# Laser_Teensy4.net
KiCad netlist of a schematic drawn in EAGLE
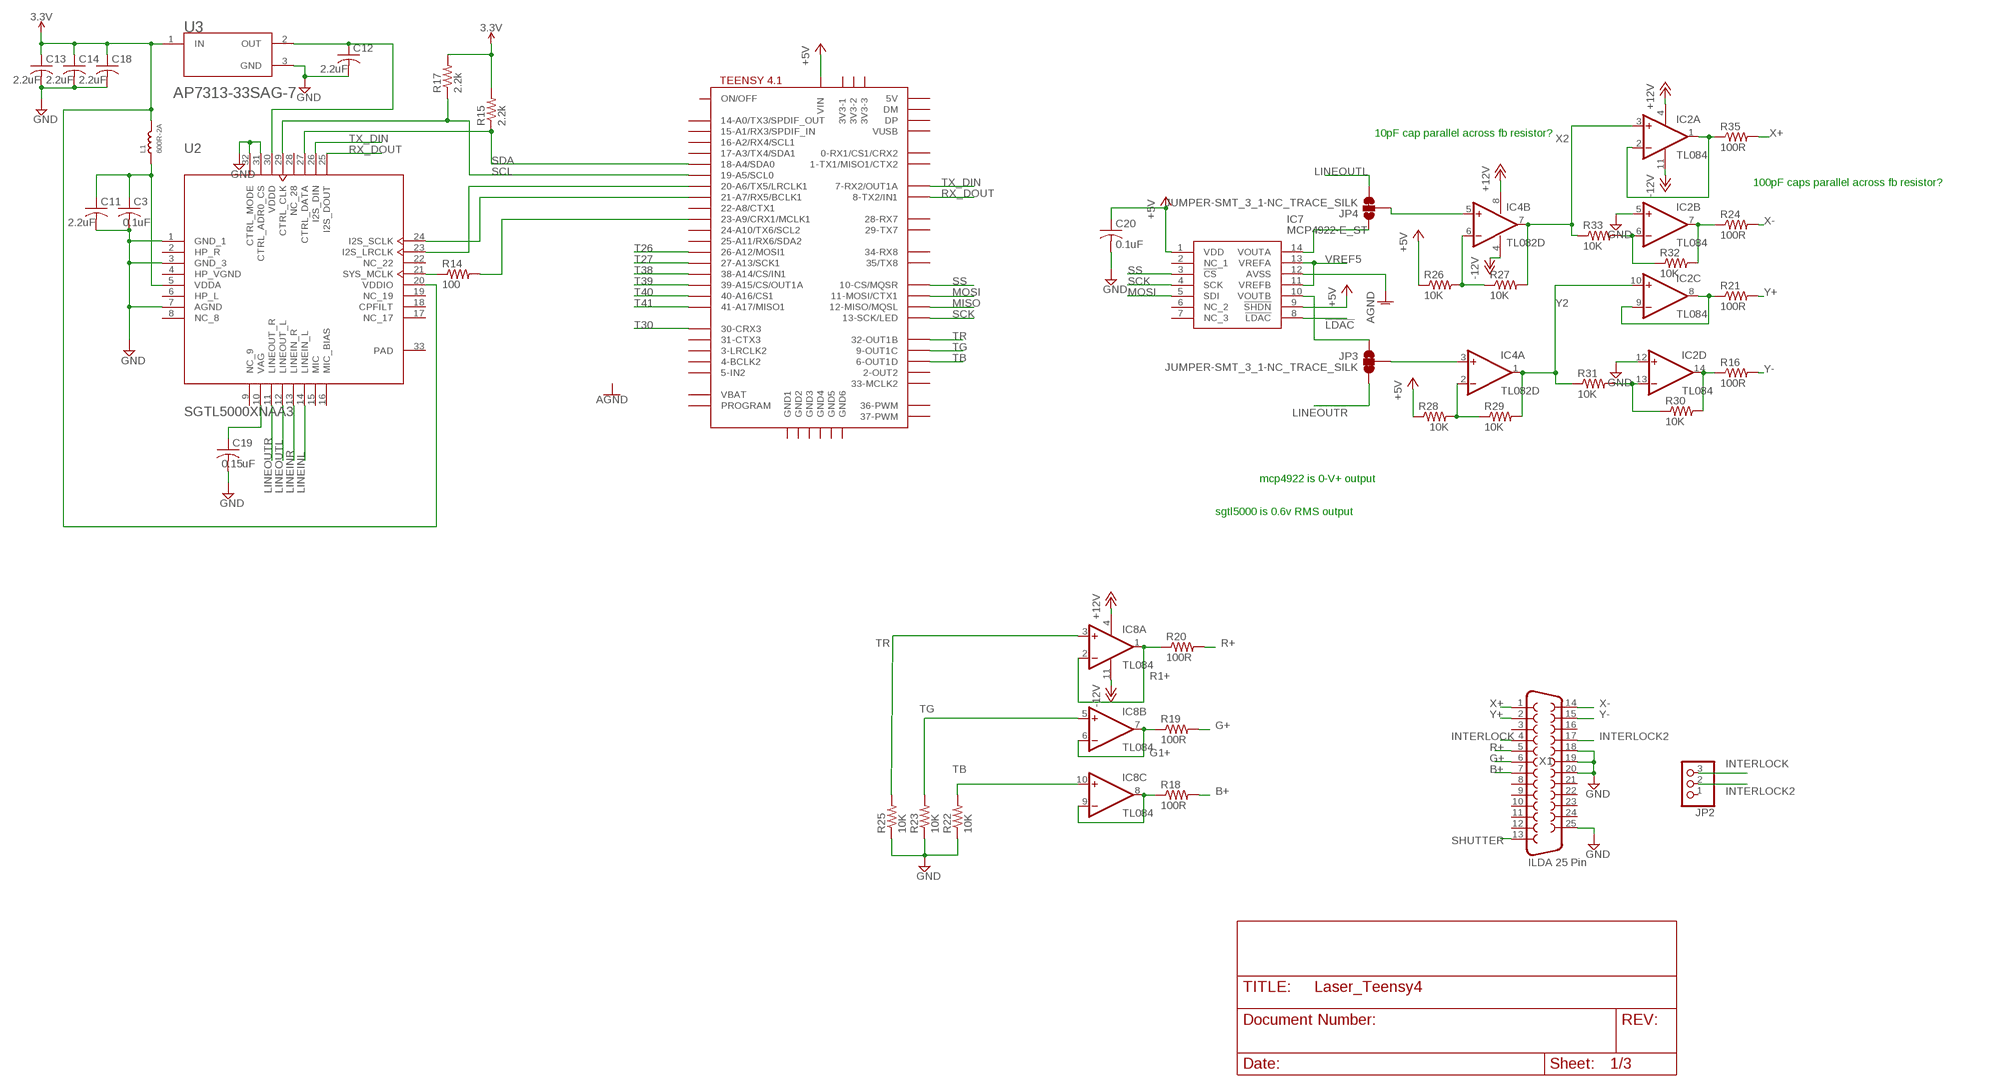
[diagram p0: schematic, sheet 1]
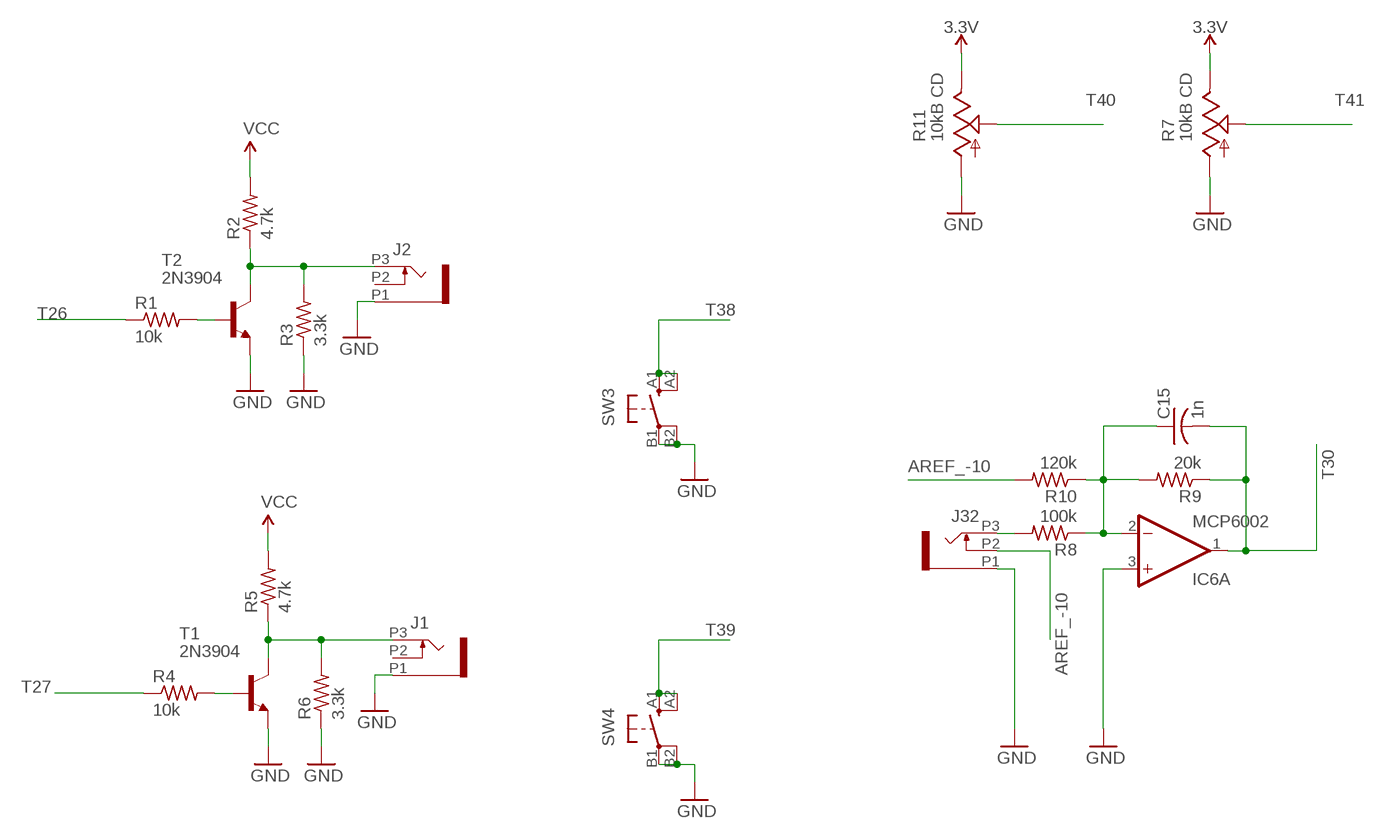
[diagram p1: schematic, sheet 2]
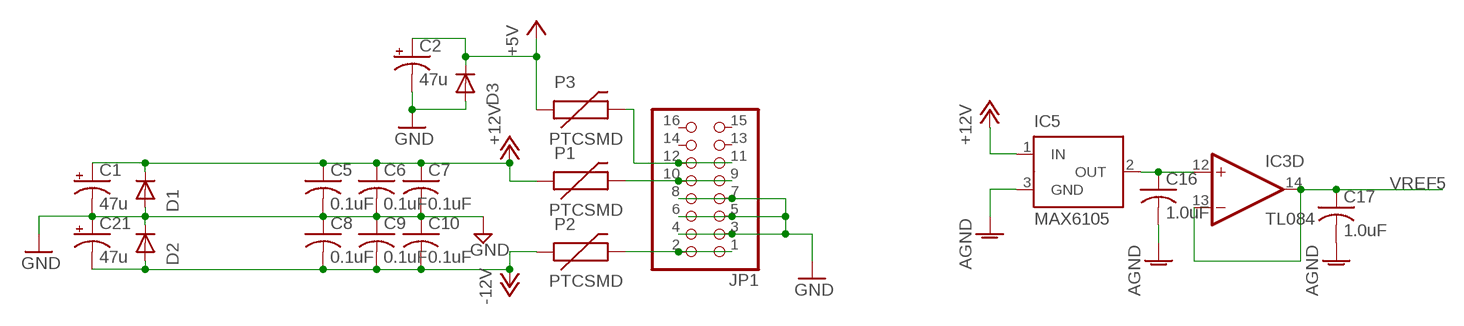
[diagram p2: schematic, sheet 3]

(export (version "E")
  (design (tool "Eeschema 10.0.6"))
  (components
    (comp (ref "C3")
      (value "0.1uF")
      (footprint "eagle-import:RCL_C0603")
      (libsource (lib "eagle-import") (part "RCL_C-USC0603"))
    )
    (comp (ref "C11")
      (value "2.2uF")
      (footprint "eagle-import:RCL_C0603")
      (libsource (lib "eagle-import") (part "RCL_C-USC0603"))
    )
    (comp (ref "C12")
      (value "2.2uF")
      (footprint "eagle-import:RCL_C0603")
      (libsource (lib "eagle-import") (part "RCL_C-USC0603"))
    )
    (comp (ref "C13")
      (value "2.2uF")
      (footprint "eagle-import:RCL_C0603")
      (libsource (lib "eagle-import") (part "RCL_C-USC0603"))
    )
    (comp (ref "C14")
      (value "2.2uF")
      (footprint "eagle-import:RCL_C0603")
      (libsource (lib "eagle-import") (part "RCL_C-USC0603"))
    )
    (comp (ref "C18")
      (value "2.2uF")
      (footprint "eagle-import:RCL_C0603")
      (libsource (lib "eagle-import") (part "RCL_C-USC0603"))
    )
    (comp (ref "C19")
      (value "0.15uF")
      (footprint "eagle-import:RCL_C0603")
      (libsource (lib "eagle-import") (part "RCL_C-USC0603"))
    )
    (comp (ref "C20")
      (value "0.1uF")
      (footprint "eagle-import:C0603")
      (libsource (lib "eagle-import") (part "C-USC0603"))
    )
    (comp (ref "IC2")
      (value "TL084")
      (footprint "eagle-import:SOIC-14")
      (libsource (lib "eagle-import") (part "TL084"))
    )
    (comp (ref "IC4")
      (value "TL082D")
      (footprint "eagle-import:SO08")
      (libsource (lib "eagle-import") (part "TL082D"))
    )
    (comp (ref "IC7")
      (value "MCP4922-E_ST")
      (footprint "eagle-import:SOP65P638X110-14N")
      (fields
        (field (name "ARROW_PART_NUMBER") "MCP4922-E/ST")
        (field (name "MOUSER_PART_NUMBER") "579-MCP4922-E/ST")
      )
      (libsource (lib "eagle-import") (part "MCP4922-E_ST"))
    )
    (comp (ref "IC8")
      (value "TL084")
      (footprint "eagle-import:SOIC-14")
      (libsource (lib "eagle-import") (part "TL084"))
    )
    (comp (ref "JP2")
      (value "PINHD-1X3")
      (footprint "eagle-import:1X03")
      (libsource (lib "eagle-import") (part "PINHD-1X3"))
    )
    (comp (ref "JP3")
      (value "JUMPER-SMT_3_1-NC_TRACE_SILK")
      (footprint "eagle-import:SMT-JUMPER_3_1-NC_TRACE_SILK")
      (libsource (lib "eagle-import") (part "JUMPER-SMT_3_1-NC_TRACE_SILK"))
    )
    (comp (ref "JP4")
      (value "JUMPER-SMT_3_1-NC_TRACE_SILK")
      (footprint "eagle-import:SMT-JUMPER_3_1-NC_TRACE_SILK")
      (libsource (lib "eagle-import") (part "JUMPER-SMT_3_1-NC_TRACE_SILK"))
    )
    (comp (ref "L1")
      (value "600R-2A")
      (footprint "eagle-import:L0805")
      (fields (field (name "MPN") "WLB2012-471T20"))
      (libsource (lib "eagle-import") (part "SMD-FERRITE-BEAD-470R-2A(0805)'0805'"))
    )
    (comp (ref "R14")
      (value "100")
      (footprint "eagle-import:R0603")
      (libsource (lib "eagle-import") (part "resistor_R-US_R0603"))
    )
    (comp (ref "R15")
      (value "2.2k")
      (footprint "eagle-import:R0603")
      (libsource (lib "eagle-import") (part "resistor_R-US_R0603"))
    )
    (comp (ref "R16")
      (value "100R")
      (footprint "eagle-import:R0603")
      (libsource (lib "eagle-import") (part "resistor_R-US_R0603"))
    )
    (comp (ref "R17")
      (value "2.2k")
      (footprint "eagle-import:R0603")
      (libsource (lib "eagle-import") (part "resistor_R-US_R0603"))
    )
    (comp (ref "R18")
      (value "100R")
      (footprint "eagle-import:R0603")
      (libsource (lib "eagle-import") (part "resistor_R-US_R0603"))
    )
    (comp (ref "R19")
      (value "100R")
      (footprint "eagle-import:R0603")
      (libsource (lib "eagle-import") (part "resistor_R-US_R0603"))
    )
    (comp (ref "R20")
      (value "100R")
      (footprint "eagle-import:R0603")
      (libsource (lib "eagle-import") (part "resistor_R-US_R0603"))
    )
    (comp (ref "R21")
      (value "100R")
      (footprint "eagle-import:R0603")
      (libsource (lib "eagle-import") (part "resistor_R-US_R0603"))
    )
    (comp (ref "R22")
      (value "10K")
      (footprint "eagle-import:R0603")
      (libsource (lib "eagle-import") (part "resistor_R-US_R0603"))
    )
    (comp (ref "R23")
      (value "10K")
      (footprint "eagle-import:R0603")
      (libsource (lib "eagle-import") (part "resistor_R-US_R0603"))
    )
    (comp (ref "R24")
      (value "100R")
      (footprint "eagle-import:R0603")
      (libsource (lib "eagle-import") (part "resistor_R-US_R0603"))
    )
    (comp (ref "R25")
      (value "10K")
      (footprint "eagle-import:R0603")
      (libsource (lib "eagle-import") (part "resistor_R-US_R0603"))
    )
    (comp (ref "R26")
      (value "10K")
      (footprint "eagle-import:R0603")
      (libsource (lib "eagle-import") (part "resistor_R-US_R0603"))
    )
    (comp (ref "R27")
      (value "10K")
      (footprint "eagle-import:R0603")
      (libsource (lib "eagle-import") (part "resistor_R-US_R0603"))
    )
    (comp (ref "R28")
      (value "10K")
      (footprint "eagle-import:R0603")
      (libsource (lib "eagle-import") (part "resistor_R-US_R0603"))
    )
    (comp (ref "R29")
      (value "10K")
      (footprint "eagle-import:R0603")
      (libsource (lib "eagle-import") (part "resistor_R-US_R0603"))
    )
    (comp (ref "R30")
      (value "10K")
      (footprint "eagle-import:R0603")
      (libsource (lib "eagle-import") (part "resistor_R-US_R0603"))
    )
    (comp (ref "R31")
      (value "10K")
      (footprint "eagle-import:R0603")
      (libsource (lib "eagle-import") (part "resistor_R-US_R0603"))
    )
    (comp (ref "R32")
      (value "10K")
      (footprint "eagle-import:R0603")
      (libsource (lib "eagle-import") (part "resistor_R-US_R0603"))
    )
    (comp (ref "R33")
      (value "10K")
      (footprint "eagle-import:R0603")
      (libsource (lib "eagle-import") (part "resistor_R-US_R0603"))
    )
    (comp (ref "R35")
      (value "100R")
      (footprint "eagle-import:R0603")
      (libsource (lib "eagle-import") (part "resistor_R-US_R0603"))
    )
    (comp (ref "U$2")
      (value "TEENSY41-E")
      (footprint "eagle-import:TENNSY41-E")
      (libsource (lib "eagle-import") (part "TEENSY41-E"))
    )
    (comp (ref "U2")
      (value "SGTL5000XNAA3")
      (footprint "eagle-import:QFN-32")
      (fields
        (field (name "DIGIKEY_PART_NUMBER") "SGTL5000XNAA3-ND")
        (field (name "MANUFACTURER") "NXP USA Inc.")
        (field (name "CREATED_BY") "PCBLayout.com")
      )
      (libsource (lib "eagle-import") (part "SGTL5000XNAA3"))
    )
    (comp (ref "U3")
      (value "DIODES_INC_AP7313-33SAG-7DIODES_INC_AP7313-33SAG-7_0_3")
      (footprint "eagle-import:DIODES_INC_AP7313-33SAG-7_3")
      (fields
        (field (name "DIGIKEY_PART_NUMBER") "AP7313-33SAG-7DICT-ND")
        (field (name "MF") "Diodes Inc.")
        (field (name "MOUSER_PART_NUMBER") "621-AP7313-33SAG-7")
      )
      (libsource (lib "eagle-import") (part "DIODES_INC_AP7313-33SAG-7DIODES_INC_AP7313-33SAG-7_0_3"))
    )
    (comp (ref "X1")
      (value "ILDA 25 Pin")
      (footprint "eagle-import:F25D")
      (libsource (lib "eagle-import") (part "F25D"))
    )
    (comp (ref "C15")
      (value "1n")
      (footprint "eagle-import:C050-025X075")
      (libsource (lib "eagle-import") (part "rcl_334_C-US050-025X075"))
    )
    (comp (ref "IC6")
      (value "MCP6002")
      (footprint "eagle-import:SO08")
      (libsource (lib "eagle-import") (part "TL072D"))
    )
    (comp (ref "J1")
      (value "PJ301_THONKICONN6")
      (footprint "eagle-import:WQP_PJ_301M6")
      (libsource (lib "eagle-import") (part "PJ301_THONKICONN6"))
    )
    (comp (ref "J2")
      (value "PJ301_THONKICONN6")
      (footprint "eagle-import:WQP_PJ_301M6")
      (libsource (lib "eagle-import") (part "PJ301_THONKICONN6"))
    )
    (comp (ref "J32")
      (value "PJ301_THONKICONN6")
      (footprint "eagle-import:WQP_PJ_301M6")
      (libsource (lib "eagle-import") (part "PJ301_THONKICONN6"))
    )
    (comp (ref "R1")
      (value "10k")
      (footprint "eagle-import:0204_7")
      (libsource (lib "eagle-import") (part "R-US_0204/7"))
    )
    (comp (ref "R2")
      (value "4.7k")
      (footprint "eagle-import:0204_7")
      (libsource (lib "eagle-import") (part "R-US_0204/7"))
    )
    (comp (ref "R3")
      (value "3.3k")
      (footprint "eagle-import:0204_7")
      (libsource (lib "eagle-import") (part "R-US_0204/7"))
    )
    (comp (ref "R4")
      (value "10k")
      (footprint "eagle-import:0204_7")
      (libsource (lib "eagle-import") (part "R-US_0204/7"))
    )
    (comp (ref "R5")
      (value "4.7k")
      (footprint "eagle-import:0204_7")
      (libsource (lib "eagle-import") (part "R-US_0204/7"))
    )
    (comp (ref "R6")
      (value "3.3k")
      (footprint "eagle-import:0204_7")
      (libsource (lib "eagle-import") (part "R-US_0204/7"))
    )
    (comp (ref "R7")
      (value "10kB CD")
      (footprint "eagle-import:ALPS_POT_VERTICAL_PS")
      (libsource (lib "eagle-import") (part "POT_USVERTICAL_PS"))
    )
    (comp (ref "R8")
      (value "100k")
      (footprint "eagle-import:0204_7")
      (libsource (lib "eagle-import") (part "R-US_0204/7"))
    )
    (comp (ref "R9")
      (value "20k")
      (footprint "eagle-import:0204_7")
      (libsource (lib "eagle-import") (part "R-US_0204/7"))
    )
    (comp (ref "R10")
      (value "120k")
      (footprint "eagle-import:0204_7")
      (libsource (lib "eagle-import") (part "R-US_0204/7"))
    )
    (comp (ref "R11")
      (value "10kB CD")
      (footprint "eagle-import:ALPS_POT_VERTICAL_PS")
      (libsource (lib "eagle-import") (part "POT_USVERTICAL_PS"))
    )
    (comp (ref "SW3")
      (value "D6R")
      (footprint "eagle-import:D6R")
      (libsource (lib "eagle-import") (part "D6R"))
    )
    (comp (ref "SW4")
      (value "D6R")
      (footprint "eagle-import:D6R")
      (libsource (lib "eagle-import") (part "D6R"))
    )
    (comp (ref "T1")
      (value "2N3904")
      (footprint "eagle-import:TO92")
      (libsource (lib "eagle-import") (part "2N3904"))
    )
    (comp (ref "T2")
      (value "2N3904")
      (footprint "eagle-import:TO92")
      (libsource (lib "eagle-import") (part "2N3904"))
    )
    (comp (ref "C1")
      (value "47u")
      (footprint "eagle-import:PANASONIC_D")
      (libsource (lib "eagle-import") (part "CPOL-USD"))
    )
    (comp (ref "C2")
      (value "47u")
      (footprint "eagle-import:PANASONIC_D")
      (libsource (lib "eagle-import") (part "CPOL-USD"))
    )
    (comp (ref "C5")
      (value "0.1uF")
      (footprint "eagle-import:C0603")
      (libsource (lib "eagle-import") (part "C-USC0603"))
    )
    (comp (ref "C6")
      (value "0.1uF")
      (footprint "eagle-import:C0603")
      (libsource (lib "eagle-import") (part "C-USC0603"))
    )
    (comp (ref "C7")
      (value "0.1uF")
      (footprint "eagle-import:C0603")
      (libsource (lib "eagle-import") (part "C-USC0603"))
    )
    (comp (ref "C8")
      (value "0.1uF")
      (footprint "eagle-import:C0603")
      (libsource (lib "eagle-import") (part "C-USC0603"))
    )
    (comp (ref "C9")
      (value "0.1uF")
      (footprint "eagle-import:C0603")
      (libsource (lib "eagle-import") (part "C-USC0603"))
    )
    (comp (ref "C10")
      (value "0.1uF")
      (footprint "eagle-import:C0603")
      (libsource (lib "eagle-import") (part "C-USC0603"))
    )
    (comp (ref "C16")
      (value "1.0uF")
      (footprint "eagle-import:C025-024X044")
      (libsource (lib "eagle-import") (part "C-US025-024X044"))
    )
    (comp (ref "C17")
      (value "1.0uF")
      (footprint "eagle-import:C025-024X044")
      (libsource (lib "eagle-import") (part "C-US025-024X044"))
    )
    (comp (ref "C21")
      (value "47u")
      (footprint "eagle-import:PANASONIC_D")
      (libsource (lib "eagle-import") (part "CPOL-USD"))
    )
    (comp (ref "D1")
      (value "1N5819HW")
      (footprint "eagle-import:SOD123")
      (libsource (lib "eagle-import") (part "DIODE-SOD123"))
    )
    (comp (ref "D2")
      (value "1N5819HW")
      (footprint "eagle-import:SOD123")
      (libsource (lib "eagle-import") (part "DIODE-SOD123"))
    )
    (comp (ref "D3")
      (value "1N5819HW")
      (footprint "eagle-import:SOD123")
      (libsource (lib "eagle-import") (part "DIODE-SOD123"))
    )
    (comp (ref "IC3")
      (value "TL084")
      (footprint "eagle-import:SOIC-14")
      (libsource (lib "eagle-import") (part "TL084"))
    )
    (comp (ref "IC5")
      (value "MAX6105")
      (footprint "eagle-import:SOT23")
      (libsource (lib "eagle-import") (part "MAX6520"))
    )
    (comp (ref "JP1")
      (value "PINHD-2X8")
      (footprint "eagle-import:2X08")
      (libsource (lib "eagle-import") (part "PINHD-2X8"))
    )
    (comp (ref "P1")
      (value "PTCSMD")
      (footprint "eagle-import:PTC-1206")
      (libsource (lib "eagle-import") (part "PTCSMD"))
    )
    (comp (ref "P2")
      (value "PTCSMD")
      (footprint "eagle-import:PTC-1206")
      (libsource (lib "eagle-import") (part "PTCSMD"))
    )
    (comp (ref "P3")
      (value "PTCSMD")
      (footprint "eagle-import:PTC-1206")
      (libsource (lib "eagle-import") (part "PTCSMD"))
    )
  )
  (nets
    (net (code "1") (name "+5V") (class "Default")
      (node (ref "C2") (pin "+") (pinfunction "+_+") (pintype "passive"))
      (node (ref "C20") (pin "1") (pinfunction "1_1") (pintype "passive"))
      (node (ref "D3") (pin "C") (pinfunction "C_C") (pintype "passive"))
      (node (ref "IC7") (pin "1") (pinfunction "VDD_1") (pintype "bidirectional"))
      (node (ref "IC7") (pin "9") (pinfunction "~{SHDN}_9") (pintype "bidirectional"))
      (node (ref "P3") (pin "1") (pinfunction "1_1") (pintype "bidirectional"))
      (node (ref "R26") (pin "1") (pinfunction "1_1") (pintype "passive"))
      (node (ref "R28") (pin "1") (pinfunction "1_1") (pintype "passive"))
      (node (ref "U$2") (pin "VIN") (pinfunction "VIN_VIN") (pintype "bidirectional"))
    )
    (net (code "2") (name "+12V") (class "Default")
      (node (ref "C1") (pin "+") (pinfunction "+_+") (pintype "passive"))
      (node (ref "C5") (pin "1") (pinfunction "1_1") (pintype "passive"))
      (node (ref "C6") (pin "1") (pinfunction "1_1") (pintype "passive"))
      (node (ref "C7") (pin "1") (pinfunction "1_1") (pintype "passive"))
      (node (ref "D1") (pin "C") (pinfunction "C_C") (pintype "passive"))
      (node (ref "IC2") (pin "4") (pinfunction "V+_4") (pintype "power_in"))
      (node (ref "IC4") (pin "8") (pinfunction "V+_8") (pintype "power_in"))
      (node (ref "IC5") (pin "1") (pinfunction "IN_1") (pintype "input"))
      (node (ref "IC8") (pin "4") (pinfunction "V+_4") (pintype "power_in"))
      (node (ref "P1") (pin "1") (pinfunction "1_1") (pintype "bidirectional"))
    )
    (net (code "3") (name "-12V") (class "Default")
      (node (ref "C10") (pin "2") (pinfunction "2_2") (pintype "passive"))
      (node (ref "C21") (pin "-") (pinfunction "-_-") (pintype "passive"))
      (node (ref "C8") (pin "2") (pinfunction "2_2") (pintype "passive"))
      (node (ref "C9") (pin "2") (pinfunction "2_2") (pintype "passive"))
      (node (ref "D2") (pin "A") (pinfunction "A_A") (pintype "passive"))
      (node (ref "IC2") (pin "11") (pinfunction "V-_11") (pintype "power_in"))
      (node (ref "IC4") (pin "4") (pinfunction "V-_4") (pintype "power_in"))
      (node (ref "IC8") (pin "11") (pinfunction "V-_11") (pintype "power_in"))
      (node (ref "P2") (pin "1") (pinfunction "1_1") (pintype "bidirectional"))
    )
    (net (code "4") (name "3.3V") (class "Default")
      (node (ref "C13") (pin "1") (pinfunction "1_1") (pintype "passive"))
      (node (ref "C14") (pin "1") (pinfunction "1_1") (pintype "passive"))
      (node (ref "C18") (pin "1") (pinfunction "1_1") (pintype "passive"))
      (node (ref "L1") (pin "2") (pinfunction "2_2") (pintype "passive"))
      (node (ref "R11") (pin "P$1") (pinfunction "E_P$1") (pintype "passive"))
      (node (ref "R15") (pin "2") (pinfunction "2_2") (pintype "passive"))
      (node (ref "R17") (pin "2") (pinfunction "2_2") (pintype "passive"))
      (node (ref "R7") (pin "P$1") (pinfunction "E_P$1") (pintype "passive"))
      (node (ref "U2") (pin "20") (pinfunction "VDDIO_20") (pintype "power_in"))
      (node (ref "U3") (pin "1") (pinfunction "IN_1") (pintype "power_in"))
    )
    (net (code "5") (name "AGND") (class "Default")
      (node (ref "C16") (pin "2") (pinfunction "2_2") (pintype "passive"))
      (node (ref "C17") (pin "2") (pinfunction "2_2") (pintype "passive"))
      (node (ref "IC5") (pin "3") (pinfunction "GND_3") (pintype "power_in"))
      (node (ref "IC7") (pin "12") (pinfunction "AVSS_12") (pintype "bidirectional"))
    )
    (net (code "6") (name "AREF_-10") (class "Default")
      (node (ref "J32") (pin "P2") (pinfunction "2_P2") (pintype "passive"))
      (node (ref "R10") (pin "2") (pinfunction "2_2") (pintype "passive"))
    )
    (net (code "7") (name "B+") (class "Default")
      (node (ref "R18") (pin "2") (pinfunction "2_2") (pintype "passive"))
      (node (ref "X1") (pin "7") (pinfunction "7_7") (pintype "passive"))
    )
    (net (code "8") (name "G+") (class "Default")
      (node (ref "R19") (pin "2") (pinfunction "2_2") (pintype "passive"))
      (node (ref "X1") (pin "6") (pinfunction "6_6") (pintype "passive"))
    )
    (net (code "9") (name "G1+") (class "Default")
      (node (ref "IC8") (pin "6") (pinfunction "-IN_6") (pintype "input"))
      (node (ref "IC8") (pin "7") (pinfunction "OUT_7") (pintype "output"))
      (node (ref "R19") (pin "1") (pinfunction "1_1") (pintype "passive"))
    )
    (net (code "10") (name "GND") (class "Default")
      (node (ref "C1") (pin "-") (pinfunction "-_-") (pintype "passive"))
      (node (ref "C10") (pin "1") (pinfunction "1_1") (pintype "passive"))
      (node (ref "C11") (pin "2") (pinfunction "2_2") (pintype "passive"))
      (node (ref "C12") (pin "2") (pinfunction "2_2") (pintype "passive"))
      (node (ref "C13") (pin "2") (pinfunction "2_2") (pintype "passive"))
      (node (ref "C14") (pin "2") (pinfunction "2_2") (pintype "passive"))
      (node (ref "C18") (pin "2") (pinfunction "2_2") (pintype "passive"))
      (node (ref "C19") (pin "2") (pinfunction "2_2") (pintype "passive"))
      (node (ref "C2") (pin "-") (pinfunction "-_-") (pintype "passive"))
      (node (ref "C20") (pin "2") (pinfunction "2_2") (pintype "passive"))
      (node (ref "C21") (pin "+") (pinfunction "+_+") (pintype "passive"))
      (node (ref "C3") (pin "2") (pinfunction "2_2") (pintype "passive"))
      (node (ref "C5") (pin "2") (pinfunction "2_2") (pintype "passive"))
      (node (ref "C6") (pin "2") (pinfunction "2_2") (pintype "passive"))
      (node (ref "C7") (pin "2") (pinfunction "2_2") (pintype "passive"))
      (node (ref "C8") (pin "1") (pinfunction "1_1") (pintype "passive"))
      (node (ref "C9") (pin "1") (pinfunction "1_1") (pintype "passive"))
      (node (ref "D1") (pin "A") (pinfunction "A_A") (pintype "passive"))
      (node (ref "D2") (pin "C") (pinfunction "C_C") (pintype "passive"))
      (node (ref "D3") (pin "A") (pinfunction "A_A") (pintype "passive"))
      (node (ref "IC2") (pin "12") (pinfunction "+IN_12") (pintype "input"))
      (node (ref "IC2") (pin "5") (pinfunction "+IN_5") (pintype "input"))
      (node (ref "IC6") (pin "3") (pinfunction "+IN_3") (pintype "input"))
      (node (ref "J1") (pin "P1") (pinfunction "1_P1") (pintype "passive"))
      (node (ref "J2") (pin "P1") (pinfunction "1_P1") (pintype "passive"))
      (node (ref "J32") (pin "P1") (pinfunction "1_P1") (pintype "passive"))
      (node (ref "JP1") (pin "3") (pinfunction "3_3") (pintype "passive"))
      (node (ref "JP1") (pin "4") (pinfunction "4_4") (pintype "passive"))
      (node (ref "JP1") (pin "5") (pinfunction "5_5") (pintype "passive"))
      (node (ref "JP1") (pin "6") (pinfunction "6_6") (pintype "passive"))
      (node (ref "JP1") (pin "7") (pinfunction "7_7") (pintype "passive"))
      (node (ref "JP1") (pin "8") (pinfunction "8_8") (pintype "passive"))
      (node (ref "R11") (pin "P$3") (pinfunction "A_P$3") (pintype "passive"))
      (node (ref "R22") (pin "1") (pinfunction "1_1") (pintype "passive"))
      (node (ref "R23") (pin "1") (pinfunction "1_1") (pintype "passive"))
      (node (ref "R25") (pin "1") (pinfunction "1_1") (pintype "passive"))
      (node (ref "R3") (pin "1") (pinfunction "1_1") (pintype "passive"))
      (node (ref "R6") (pin "1") (pinfunction "1_1") (pintype "passive"))
      (node (ref "R7") (pin "P$3") (pinfunction "A_P$3") (pintype "passive"))
      (node (ref "SW3") (pin "B1") (pinfunction "P_B1") (pintype "passive"))
      (node (ref "SW3") (pin "B2") (pinfunction "P1_B2") (pintype "passive"))
      (node (ref "SW4") (pin "B1") (pinfunction "P_B1") (pintype "passive"))
      (node (ref "SW4") (pin "B2") (pinfunction "P1_B2") (pintype "passive"))
      (node (ref "T1") (pin "3") (pinfunction "E_3") (pintype "passive"))
      (node (ref "T2") (pin "3") (pinfunction "E_3") (pintype "passive"))
      (node (ref "U2") (pin "1") (pinfunction "GND_1_1") (pintype "power_in"))
      (node (ref "U2") (pin "3") (pinfunction "GND_3_3") (pintype "power_in"))
      (node (ref "U2") (pin "31") (pinfunction "CTRL_ADR0_CS_31") (pintype "input"))
      (node (ref "U2") (pin "32") (pinfunction "CTRL_MODE_32") (pintype "bidirectional"))
      (node (ref "U2") (pin "7") (pinfunction "AGND_7") (pintype "power_in"))
      (node (ref "U3") (pin "3") (pinfunction "GND_3") (pintype "power_in"))
      (node (ref "X1") (pin "18") (pinfunction "18_18") (pintype "passive"))
      (node (ref "X1") (pin "19") (pinfunction "19_19") (pintype "passive"))
      (node (ref "X1") (pin "20") (pinfunction "20_20") (pintype "passive"))
      (node (ref "X1") (pin "25") (pinfunction "25_25") (pintype "passive"))
    )
    (net (code "11") (name "HP_VGND") (class "Default")
      (node (ref "U2") (pin "4") (pinfunction "HP_VGND_4") (pintype "power_in"))
    )
    (net (code "12") (name "INTERLOCK") (class "Default")
      (node (ref "JP2") (pin "3") (pinfunction "3_3") (pintype "passive"))
      (node (ref "X1") (pin "4") (pinfunction "4_4") (pintype "passive"))
    )
    (net (code "13") (name "INTERLOCK2") (class "Default")
      (node (ref "JP2") (pin "2") (pinfunction "2_2") (pintype "passive"))
      (node (ref "X1") (pin "17") (pinfunction "17_17") (pintype "passive"))
    )
    (net (code "14") (name "LINEINL") (class "Default")
      (node (ref "U2") (pin "14") (pinfunction "LINEIN_L_14") (pintype "input"))
    )
    (net (code "15") (name "LINEINR") (class "Default")
      (node (ref "U2") (pin "13") (pinfunction "LINEIN_R_13") (pintype "input"))
    )
    (net (code "16") (name "LINEOUTL") (class "Default")
      (node (ref "JP4") (pin "3") (pinfunction "3_3") (pintype "passive"))
      (node (ref "U2") (pin "12") (pinfunction "LINEOUT_L_12") (pintype "output"))
    )
    (net (code "17") (name "LINEOUTR") (class "Default")
      (node (ref "JP3") (pin "3") (pinfunction "3_3") (pintype "passive"))
      (node (ref "U2") (pin "11") (pinfunction "LINEOUT_R_11") (pintype "output"))
    )
    (net (code "18") (name "MISO") (class "Default")
      (node (ref "U$2") (pin "12-MISO/MQSL") (pinfunction "12-MISO/MQSL_12-MISO/MQSL") (pintype "bidirectional"))
    )
    (net (code "19") (name "MOSI") (class "Default")
      (node (ref "IC7") (pin "5") (pinfunction "SDI_5") (pintype "bidirectional"))
      (node (ref "U$2") (pin "11-MOSI/CTX1") (pinfunction "11-MOSI/CTX1_11-MOSI/CTX1") (pintype "bidirectional"))
    )
    (net (code "20") (name "Net-(IC2A--IN)") (class "Default")
      (node (ref "IC2") (pin "1") (pinfunction "OUT_1") (pintype "output"))
      (node (ref "IC2") (pin "2") (pinfunction "-IN_2") (pintype "input"))
      (node (ref "R35") (pin "1") (pinfunction "1_1") (pintype "passive"))
    )
    (net (code "21") (name "Net-(IC2B--IN)") (class "Default")
      (node (ref "IC2") (pin "6") (pinfunction "-IN_6") (pintype "input"))
      (node (ref "R32") (pin "1") (pinfunction "1_1") (pintype "passive"))
      (node (ref "R33") (pin "2") (pinfunction "2_2") (pintype "passive"))
    )
    (net (code "22") (name "Net-(IC2B-OUT)") (class "Default")
      (node (ref "IC2") (pin "7") (pinfunction "OUT_7") (pintype "output"))
      (node (ref "R24") (pin "1") (pinfunction "1_1") (pintype "passive"))
      (node (ref "R32") (pin "2") (pinfunction "2_2") (pintype "passive"))
    )
    (net (code "23") (name "Net-(IC2C--IN)") (class "Default")
      (node (ref "IC2") (pin "8") (pinfunction "OUT_8") (pintype "output"))
      (node (ref "IC2") (pin "9") (pinfunction "-IN_9") (pintype "input"))
      (node (ref "R21") (pin "1") (pinfunction "1_1") (pintype "passive"))
    )
    (net (code "24") (name "Net-(IC2D--IN)") (class "Default")
      (node (ref "IC2") (pin "13") (pinfunction "-IN_13") (pintype "input"))
      (node (ref "R30") (pin "1") (pinfunction "1_1") (pintype "passive"))
      (node (ref "R31") (pin "2") (pinfunction "2_2") (pintype "passive"))
    )
    (net (code "25") (name "Net-(IC2D-OUT)") (class "Default")
      (node (ref "IC2") (pin "14") (pinfunction "OUT_14") (pintype "output"))
      (node (ref "R16") (pin "1") (pinfunction "1_1") (pintype "passive"))
      (node (ref "R30") (pin "2") (pinfunction "2_2") (pintype "passive"))
    )
    (net (code "26") (name "Net-(IC3D-+IN)") (class "Default")
      (node (ref "C16") (pin "1") (pinfunction "1_1") (pintype "passive"))
      (node (ref "IC3") (pin "12") (pinfunction "+IN_12") (pintype "input"))
      (node (ref "IC5") (pin "2") (pinfunction "OUT_2") (pintype "input"))
    )
    (net (code "27") (name "Net-(IC4A-+IN)") (class "Default")
      (node (ref "IC4") (pin "3") (pinfunction "+IN_3") (pintype "input"))
      (node (ref "JP3") (pin "2") (pinfunction "2_2") (pintype "passive"))
    )
    (net (code "28") (name "Net-(IC4A--IN)") (class "Default")
      (node (ref "IC4") (pin "2") (pinfunction "-IN_2") (pintype "input"))
      (node (ref "R28") (pin "2") (pinfunction "2_2") (pintype "passive"))
      (node (ref "R29") (pin "1") (pinfunction "1_1") (pintype "passive"))
    )
    (net (code "29") (name "Net-(IC4B-+IN)") (class "Default")
      (node (ref "IC4") (pin "5") (pinfunction "+IN_5") (pintype "input"))
      (node (ref "JP4") (pin "2") (pinfunction "2_2") (pintype "passive"))
    )
    (net (code "30") (name "Net-(IC4B--IN)") (class "Default")
      (node (ref "IC4") (pin "6") (pinfunction "-IN_6") (pintype "input"))
      (node (ref "R26") (pin "2") (pinfunction "2_2") (pintype "passive"))
      (node (ref "R27") (pin "1") (pinfunction "1_1") (pintype "passive"))
    )
    (net (code "31") (name "Net-(IC6A--IN)") (class "Default")
      (node (ref "C15") (pin "1") (pinfunction "1_1") (pintype "passive"))
      (node (ref "IC6") (pin "2") (pinfunction "-IN_2") (pintype "input"))
      (node (ref "R10") (pin "1") (pinfunction "1_1") (pintype "passive"))
      (node (ref "R8") (pin "1") (pinfunction "1_1") (pintype "passive"))
      (node (ref "R9") (pin "2") (pinfunction "2_2") (pintype "passive"))
    )
    (net (code "32") (name "Net-(IC7-VOUTA)") (class "Default")
      (node (ref "IC7") (pin "14") (pinfunction "VOUTA_14") (pintype "bidirectional"))
      (node (ref "JP4") (pin "1") (pinfunction "1_1") (pintype "passive"))
    )
    (net (code "33") (name "Net-(IC7-VOUTB)") (class "Default")
      (node (ref "IC7") (pin "10") (pinfunction "VOUTB_10") (pintype "bidirectional"))
      (node (ref "JP3") (pin "1") (pinfunction "1_1") (pintype "passive"))
    )
    (net (code "34") (name "Net-(IC8C--IN)") (class "Default")
      (node (ref "IC8") (pin "8") (pinfunction "OUT_8") (pintype "output"))
      (node (ref "IC8") (pin "9") (pinfunction "-IN_9") (pintype "input"))
      (node (ref "R18") (pin "1") (pinfunction "1_1") (pintype "passive"))
    )
    (net (code "35") (name "Net-(J1-3)") (class "Default")
      (node (ref "J1") (pin "P3") (pinfunction "3_P3") (pintype "passive"))
      (node (ref "R5") (pin "1") (pinfunction "1_1") (pintype "passive"))
      (node (ref "R6") (pin "2") (pinfunction "2_2") (pintype "passive"))
      (node (ref "T1") (pin "1") (pinfunction "C_1") (pintype "passive"))
    )
    (net (code "36") (name "Net-(J2-3)") (class "Default")
      (node (ref "J2") (pin "P3") (pinfunction "3_P3") (pintype "passive"))
      (node (ref "R2") (pin "1") (pinfunction "1_1") (pintype "passive"))
      (node (ref "R3") (pin "2") (pinfunction "2_2") (pintype "passive"))
      (node (ref "T2") (pin "1") (pinfunction "C_1") (pintype "passive"))
    )
    (net (code "37") (name "Net-(J32-3)") (class "Default")
      (node (ref "J32") (pin "P3") (pinfunction "3_P3") (pintype "passive"))
      (node (ref "R8") (pin "2") (pinfunction "2_2") (pintype "passive"))
    )
    (net (code "38") (name "Net-(JP1-Pad1)") (class "Default")
      (node (ref "JP1") (pin "1") (pinfunction "1_1") (pintype "passive"))
      (node (ref "JP1") (pin "2") (pinfunction "2_2") (pintype "passive"))
      (node (ref "P2") (pin "2") (pinfunction "2_2") (pintype "bidirectional"))
    )
    (net (code "39") (name "Net-(JP1-Pad10)") (class "Default")
      (node (ref "JP1") (pin "10") (pinfunction "10_10") (pintype "passive"))
      (node (ref "JP1") (pin "9") (pinfunction "9_9") (pintype "passive"))
      (node (ref "P1") (pin "2") (pinfunction "2_2") (pintype "bidirectional"))
    )
    (net (code "40") (name "Net-(JP1-Pad11)") (class "Default")
      (node (ref "JP1") (pin "11") (pinfunction "11_11") (pintype "passive"))
      (node (ref "JP1") (pin "12") (pinfunction "12_12") (pintype "passive"))
      (node (ref "P3") (pin "2") (pinfunction "2_2") (pintype "bidirectional"))
    )
    (net (code "41") (name "Net-(R14-Pad2)") (class "Default")
      (node (ref "R14") (pin "2") (pinfunction "2_2") (pintype "passive"))
      (node (ref "U$2") (pin "23-A9/CRX1/MCLK1") (pinfunction "23-A9/CRX1/MCLK1_23-A9/CRX1/MCLK1") (pintype "bidirectional"))
    )
    (net (code "42") (name "Net-(T1-B)") (class "Default")
      (node (ref "R4") (pin "2") (pinfunction "2_2") (pintype "passive"))
      (node (ref "T1") (pin "2") (pinfunction "B_2") (pintype "passive"))
    )
    (net (code "43") (name "Net-(T2-B)") (class "Default")
      (node (ref "R1") (pin "2") (pinfunction "2_2") (pintype "passive"))
      (node (ref "T2") (pin "2") (pinfunction "B_2") (pintype "passive"))
    )
    (net (code "44") (name "Net-(U2-I2S_LRCLK)") (class "Default")
      (node (ref "U$2") (pin "20-A6/TX5/LRCLK1") (pinfunction "20-A6/TX5/LRCLK1_20-A6/TX5/LRCLK1") (pintype "bidirectional"))
      (node (ref "U2") (pin "23") (pinfunction "I2S_LRCLK_23") (pintype "input"))
    )
    (net (code "45") (name "Net-(U2-I2S_SCLK)") (class "Default")
      (node (ref "U$2") (pin "21-A7/RX5/BCLK1") (pinfunction "21-A7/RX5/BCLK1_21-A7/RX5/BCLK1") (pintype "bidirectional"))
      (node (ref "U2") (pin "24") (pinfunction "I2S_SCLK_24") (pintype "input"))
    )
    (net (code "46") (name "Net-(U2-SYS_MCLK)") (class "Default")
      (node (ref "R14") (pin "1") (pinfunction "1_1") (pintype "passive"))
      (node (ref "U2") (pin "21") (pinfunction "SYS_MCLK_21") (pintype "input"))
    )
    (net (code "47") (name "Net-(U2-VAG)") (class "Default")
      (node (ref "C19") (pin "1") (pinfunction "1_1") (pintype "passive"))
      (node (ref "U2") (pin "10") (pinfunction "VAG_10") (pintype "bidirectional"))
    )
    (net (code "48") (name "Net-(U2-VDDA)") (class "Default")
      (node (ref "C11") (pin "1") (pinfunction "1_1") (pintype "passive"))
      (node (ref "C3") (pin "1") (pinfunction "1_1") (pintype "passive"))
      (node (ref "L1") (pin "1") (pinfunction "1_1") (pintype "passive"))
      (node (ref "U2") (pin "5") (pinfunction "VDDA_5") (pintype "power_in"))
    )
    (net (code "49") (name "Net-(U2-VDDD)") (class "Default")
      (node (ref "C12") (pin "1") (pinfunction "1_1") (pintype "passive"))
      (node (ref "U2") (pin "30") (pinfunction "VDDD_30") (pintype "power_in"))
      (node (ref "U3") (pin "2") (pinfunction "OUT_2") (pintype "power_in"))
    )
    (net (code "50") (name "PAD") (class "Default")
      (node (ref "U2") (pin "33") (pinfunction "PAD_33") (pintype "power_in"))
    )
    (net (code "51") (name "R+") (class "Default")
      (node (ref "R20") (pin "2") (pinfunction "2_2") (pintype "passive"))
      (node (ref "X1") (pin "5") (pinfunction "5_5") (pintype "passive"))
    )
    (net (code "52") (name "R1+") (class "Default")
      (node (ref "IC8") (pin "1") (pinfunction "OUT_1") (pintype "output"))
      (node (ref "IC8") (pin "2") (pinfunction "-IN_2") (pintype "input"))
      (node (ref "R20") (pin "1") (pinfunction "1_1") (pintype "passive"))
    )
    (net (code "53") (name "RX_DOUT") (class "Default")
      (node (ref "U$2") (pin "8-TX2/IN1") (pinfunction "8-TX2/IN1_8-TX2/IN1") (pintype "bidirectional"))
      (node (ref "U2") (pin "25") (pinfunction "I2S_DOUT_25") (pintype "output"))
    )
    (net (code "54") (name "SCK") (class "Default")
      (node (ref "IC7") (pin "4") (pinfunction "SCK_4") (pintype "bidirectional"))
      (node (ref "U$2") (pin "13-SCK/LED") (pinfunction "13-SCK/LED_13-SCK/LED") (pintype "bidirectional"))
    )
    (net (code "55") (name "SCL") (class "Default")
      (node (ref "R17") (pin "1") (pinfunction "1_1") (pintype "passive"))
      (node (ref "U$2") (pin "19-A5/SCL0") (pinfunction "19-A5/SCL0_19-A5/SCL0") (pintype "bidirectional"))
      (node (ref "U2") (pin "29") (pinfunction "CTRL_CLK_29") (pintype "bidirectional"))
    )
    (net (code "56") (name "SDA") (class "Default")
      (node (ref "R15") (pin "1") (pinfunction "1_1") (pintype "passive"))
      (node (ref "U$2") (pin "18-A4/SDA0") (pinfunction "18-A4/SDA0_18-A4/SDA0") (pintype "bidirectional"))
      (node (ref "U2") (pin "27") (pinfunction "CTRL_DATA_27") (pintype "input"))
    )
    (net (code "57") (name "SHUTTER") (class "Default")
      (node (ref "X1") (pin "13") (pinfunction "13_13") (pintype "passive"))
    )
    (net (code "58") (name "SS") (class "Default")
      (node (ref "IC7") (pin "3") (pinfunction "~{CS}_3") (pintype "bidirectional"))
      (node (ref "U$2") (pin "10-CS\\MQSR") (pinfunction "10-CS/MQSR_10-CS\\MQSR") (pintype "bidirectional"))
    )
    (net (code "59") (name "T26") (class "Default")
      (node (ref "R1") (pin "1") (pinfunction "1_1") (pintype "passive"))
      (node (ref "U$2") (pin "26-A12/MOSI1") (pinfunction "26-A12/MOSI1_26-A12/MOSI1") (pintype "bidirectional"))
    )
    (net (code "60") (name "T27") (class "Default")
      (node (ref "R4") (pin "1") (pinfunction "1_1") (pintype "passive"))
      (node (ref "U$2") (pin "27-A13/SCK1") (pinfunction "27-A13/SCK1_27-A13/SCK1") (pintype "bidirectional"))
    )
    (net (code "61") (name "T30") (class "Default")
      (node (ref "C15") (pin "2") (pinfunction "2_2") (pintype "passive"))
      (node (ref "IC6") (pin "1") (pinfunction "OUT_1") (pintype "output"))
      (node (ref "R9") (pin "1") (pinfunction "1_1") (pintype "passive"))
      (node (ref "U$2") (pin "30-CRX3") (pinfunction "30-CRX3_30-CRX3") (pintype "bidirectional"))
    )
    (net (code "62") (name "T38") (class "Default")
      (node (ref "SW3") (pin "A1") (pinfunction "S_A1") (pintype "passive"))
      (node (ref "SW3") (pin "A2") (pinfunction "S1_A2") (pintype "passive"))
      (node (ref "U$2") (pin "38-A14/CS/IN1") (pinfunction "38-A14/CS/IN1_38-A14/CS/IN1") (pintype "bidirectional"))
    )
    (net (code "63") (name "T39") (class "Default")
      (node (ref "SW4") (pin "A1") (pinfunction "S_A1") (pintype "passive"))
      (node (ref "SW4") (pin "A2") (pinfunction "S1_A2") (pintype "passive"))
      (node (ref "U$2") (pin "39-A15/CS/OUT1A") (pinfunction "39-A15/CS/OUT1A_39-A15/CS/OUT1A") (pintype "bidirectional"))
    )
    (net (code "64") (name "T40") (class "Default")
      (node (ref "R11") (pin "P$2") (pinfunction "S_P$2") (pintype "passive"))
      (node (ref "U$2") (pin "40-A16/CS1") (pinfunction "40-A16/CS1_40-A16/CS1") (pintype "bidirectional"))
    )
    (net (code "65") (name "T41") (class "Default")
      (node (ref "R7") (pin "P$2") (pinfunction "S_P$2") (pintype "passive"))
      (node (ref "U$2") (pin "41-A17/MISO1") (pinfunction "41-A17/MISO1_41-A17/MISO1") (pintype "bidirectional"))
    )
    (net (code "66") (name "TB") (class "Default")
      (node (ref "IC8") (pin "10") (pinfunction "+IN_10") (pintype "input"))
      (node (ref "R22") (pin "2") (pinfunction "2_2") (pintype "passive"))
      (node (ref "U$2") (pin "6-OUT1D") (pinfunction "6-OUT1D_6-OUT1D") (pintype "bidirectional"))
    )
    (net (code "67") (name "TG") (class "Default")
      (node (ref "IC8") (pin "5") (pinfunction "+IN_5") (pintype "input"))
      (node (ref "R23") (pin "2") (pinfunction "2_2") (pintype "passive"))
      (node (ref "U$2") (pin "9-OUT1C") (pinfunction "9-OUT1C_9-OUT1C") (pintype "bidirectional"))
    )
    (net (code "68") (name "TR") (class "Default")
      (node (ref "IC8") (pin "3") (pinfunction "+IN_3") (pintype "input"))
      (node (ref "R25") (pin "2") (pinfunction "2_2") (pintype "passive"))
      (node (ref "U$2") (pin "32-OUT1B") (pinfunction "32-OUT1B_32-OUT1B") (pintype "bidirectional"))
    )
    (net (code "69") (name "TX_DIN") (class "Default")
      (node (ref "U$2") (pin "7-RX2/OUT1A") (pinfunction "7-RX2/OUT1A_7-RX2/OUT1A") (pintype "bidirectional"))
      (node (ref "U2") (pin "26") (pinfunction "I2S_DIN_26") (pintype "input"))
    )
    (net (code "70") (name "VCC") (class "Default")
      (node (ref "R2") (pin "2") (pinfunction "2_2") (pintype "passive"))
      (node (ref "R5") (pin "2") (pinfunction "2_2") (pintype "passive"))
    )
    (net (code "71") (name "VREF5") (class "Default")
      (node (ref "C17") (pin "1") (pinfunction "1_1") (pintype "passive"))
      (node (ref "IC3") (pin "13") (pinfunction "-IN_13") (pintype "input"))
      (node (ref "IC3") (pin "14") (pinfunction "OUT_14") (pintype "output"))
      (node (ref "IC7") (pin "11") (pinfunction "VREFB_11") (pintype "bidirectional"))
      (node (ref "IC7") (pin "13") (pinfunction "VREFA_13") (pintype "bidirectional"))
    )
    (net (code "72") (name "X+") (class "Default")
      (node (ref "R35") (pin "2") (pinfunction "2_2") (pintype "passive"))
      (node (ref "X1") (pin "1") (pinfunction "1_1") (pintype "passive"))
    )
    (net (code "73") (name "X-") (class "Default")
      (node (ref "R24") (pin "2") (pinfunction "2_2") (pintype "passive"))
      (node (ref "X1") (pin "14") (pinfunction "14_14") (pintype "passive"))
    )
    (net (code "74") (name "X2") (class "Default")
      (node (ref "IC2") (pin "3") (pinfunction "+IN_3") (pintype "input"))
      (node (ref "IC4") (pin "7") (pinfunction "OUT_7") (pintype "output"))
      (node (ref "R27") (pin "2") (pinfunction "2_2") (pintype "passive"))
      (node (ref "R33") (pin "1") (pinfunction "1_1") (pintype "passive"))
    )
    (net (code "75") (name "Y+") (class "Default")
      (node (ref "R21") (pin "2") (pinfunction "2_2") (pintype "passive"))
      (node (ref "X1") (pin "2") (pinfunction "2_2") (pintype "passive"))
    )
    (net (code "76") (name "Y-") (class "Default")
      (node (ref "R16") (pin "2") (pinfunction "2_2") (pintype "passive"))
      (node (ref "X1") (pin "15") (pinfunction "15_15") (pintype "passive"))
    )
    (net (code "77") (name "Y2") (class "Default")
      (node (ref "IC2") (pin "10") (pinfunction "+IN_10") (pintype "input"))
      (node (ref "IC4") (pin "1") (pinfunction "OUT_1") (pintype "output"))
      (node (ref "R29") (pin "2") (pinfunction "2_2") (pintype "passive"))
      (node (ref "R31") (pin "1") (pinfunction "1_1") (pintype "passive"))
    )
    (net (code "78") (name "unconnected-(IC7-NC_1-Pad2)") (class "Default")
      (node (ref "IC7") (pin "2") (pinfunction "NC_1_2") (pintype "bidirectional"))
    )
    (net (code "79") (name "unconnected-(IC7-NC_2-Pad6)") (class "Default")
      (node (ref "IC7") (pin "6") (pinfunction "NC_2_6") (pintype "bidirectional"))
    )
    (net (code "80") (name "unconnected-(IC7-NC_3-Pad7)") (class "Default")
      (node (ref "IC7") (pin "7") (pinfunction "NC_3_7") (pintype "bidirectional"))
    )
    (net (code "81") (name "unconnected-(J1-2-PadP2)") (class "Default")
      (node (ref "J1") (pin "P2") (pinfunction "2_P2") (pintype "passive"))
    )
    (net (code "82") (name "unconnected-(J2-2-PadP2)") (class "Default")
      (node (ref "J2") (pin "P2") (pinfunction "2_P2") (pintype "passive"))
    )
    (net (code "83") (name "unconnected-(JP1-Pad13)") (class "Default")
      (node (ref "JP1") (pin "13") (pinfunction "13_13") (pintype "passive"))
    )
    (net (code "84") (name "unconnected-(JP1-Pad14)") (class "Default")
      (node (ref "JP1") (pin "14") (pinfunction "14_14") (pintype "passive"))
    )
    (net (code "85") (name "unconnected-(JP1-Pad15)") (class "Default")
      (node (ref "JP1") (pin "15") (pinfunction "15_15") (pintype "passive"))
    )
    (net (code "86") (name "unconnected-(JP1-Pad16)") (class "Default")
      (node (ref "JP1") (pin "16") (pinfunction "16_16") (pintype "passive"))
    )
    (net (code "87") (name "unconnected-(JP2-Pad1)") (class "Default")
      (node (ref "JP2") (pin "1") (pinfunction "1_1") (pintype "passive"))
    )
    (net (code "88") (name "unconnected-(U$2-5V-Pad+5V)") (class "Default")
      (node (ref "U$2") (pin "+5V") (pinfunction "5V_+5V") (pintype "bidirectional"))
    )
    (net (code "89") (name "unconnected-(U$2-35{slash}TX8-Pad35-TX8)") (class "Default")
      (node (ref "U$2") (pin "35-TX8") (pinfunction "35/TX8_35-TX8") (pintype "bidirectional"))
    )
    (net (code "90") (name "unconnected-(U$2-Pad0-RX1{slash}CS1{slash}CRX2)") (class "Default")
      (node (ref "U$2") (pin "0-RX1/CS1/CRX2") (pinfunction "0-RX1/CS1/CRX2_0-RX1/CS1/CRX2") (pintype "bidirectional"))
    )
    (net (code "91") (name "unconnected-(U$2-Pad1-TX1{slash}MISO1{slash}CTX2)") (class "Default")
      (node (ref "U$2") (pin "1-TX1/MISO1/CTX2") (pinfunction "1-TX1/MISO1/CTX2_1-TX1/MISO1/CTX2") (pintype "bidirectional"))
    )
    (net (code "92") (name "unconnected-(U$2-Pad2-OUT2)") (class "Default")
      (node (ref "U$2") (pin "2-OUT2") (pinfunction "2-OUT2_2-OUT2") (pintype "bidirectional"))
    )
    (net (code "93") (name "unconnected-(U$2-Pad3-LRCLK2)") (class "Default")
      (node (ref "U$2") (pin "3-LRCLK2") (pinfunction "3-LRCLK2_3-LRCLK2") (pintype "bidirectional"))
    )
    (net (code "94") (name "unconnected-(U$2-Pad3V3-1)") (class "Default")
      (node (ref "U$2") (pin "3V3-1") (pinfunction "3V3-1_3V3-1") (pintype "bidirectional"))
    )
    (net (code "95") (name "unconnected-(U$2-Pad3V3-2)") (class "Default")
      (node (ref "U$2") (pin "3V3-2") (pinfunction "3V3-2_3V3-2") (pintype "bidirectional"))
    )
    (net (code "96") (name "unconnected-(U$2-Pad3V3-3)") (class "Default")
      (node (ref "U$2") (pin "3V3-3") (pinfunction "3V3-3_3V3-3") (pintype "bidirectional"))
    )
    (net (code "97") (name "unconnected-(U$2-Pad4-BCLK2)") (class "Default")
      (node (ref "U$2") (pin "4-BCLK2") (pinfunction "4-BCLK2_4-BCLK2") (pintype "bidirectional"))
    )
    (net (code "98") (name "unconnected-(U$2-Pad5-IN2)") (class "Default")
      (node (ref "U$2") (pin "5-IN2") (pinfunction "5-IN2_5-IN2") (pintype "bidirectional"))
    )
    (net (code "99") (name "unconnected-(U$2-Pad14-A0{slash}TX3{slash}SPDIF_OUT)") (class "Default")
      (node (ref "U$2") (pin "14-A0/TX3/SPDIF_OUT") (pinfunction "14-A0/TX3/SPDIF_OUT_14-A0/TX3/SPDIF_OUT") (pintype "bidirectional"))
    )
    (net (code "100") (name "unconnected-(U$2-Pad15-A1{slash}RX3{slash}SPDIF_IN)") (class "Default")
      (node (ref "U$2") (pin "15-A1/RX3/SPDIF_IN") (pinfunction "15-A1/RX3/SPDIF_IN_15-A1/RX3/SPDIF_IN") (pintype "bidirectional"))
    )
    (net (code "101") (name "unconnected-(U$2-Pad16-A2{slash}RX4{slash}SCL1)") (class "Default")
      (node (ref "U$2") (pin "16-A2/RX4/SCL1") (pinfunction "16-A2/RX4/SCL1_16-A2/RX4/SCL1") (pintype "bidirectional"))
    )
    (net (code "102") (name "unconnected-(U$2-Pad17-A3{slash}TX4{slash}SDA1)") (class "Default")
      (node (ref "U$2") (pin "17-A3/TX4/SDA1") (pinfunction "17-A3/TX4/SDA1_17-A3/TX4/SDA1") (pintype "bidirectional"))
    )
    (net (code "103") (name "unconnected-(U$2-Pad22-A8{slash}CTX1)") (class "Default")
      (node (ref "U$2") (pin "22-A8/CTX1") (pinfunction "22-A8/CTX1_22-A8/CTX1") (pintype "bidirectional"))
    )
    (net (code "104") (name "unconnected-(U$2-Pad24-A10{slash}TX6{slash}SCL2)") (class "Default")
      (node (ref "U$2") (pin "24-A10/TX6/SCL2") (pinfunction "24-A10/TX6/SCL2_24-A10/TX6/SCL2") (pintype "bidirectional"))
    )
    (net (code "105") (name "unconnected-(U$2-Pad25-A11{slash}RX6{slash}SDA2)") (class "Default")
      (node (ref "U$2") (pin "25-A11/RX6/SDA2") (pinfunction "25-A11/RX6/SDA2_25-A11/RX6/SDA2") (pintype "bidirectional"))
    )
    (net (code "106") (name "unconnected-(U$2-Pad28-RX7)") (class "Default")
      (node (ref "U$2") (pin "28-RX7") (pinfunction "28-RX7_28-RX7") (pintype "bidirectional"))
    )
    (net (code "107") (name "unconnected-(U$2-Pad29-TX7)") (class "Default")
      (node (ref "U$2") (pin "29-TX7") (pinfunction "29-TX7_29-TX7") (pintype "bidirectional"))
    )
    (net (code "108") (name "unconnected-(U$2-Pad31-CTX3)") (class "Default")
      (node (ref "U$2") (pin "31-CTX3") (pinfunction "31-CTX3_31-CTX3") (pintype "bidirectional"))
    )
    (net (code "109") (name "unconnected-(U$2-Pad33-MCLK2)") (class "Default")
      (node (ref "U$2") (pin "33-MCLK2") (pinfunction "33-MCLK2_33-MCLK2") (pintype "bidirectional"))
    )
    (net (code "110") (name "unconnected-(U$2-Pad34-RX8)") (class "Default")
      (node (ref "U$2") (pin "34-RX8") (pinfunction "34-RX8_34-RX8") (pintype "bidirectional"))
    )
    (net (code "111") (name "unconnected-(U$2-Pad36-PWM)") (class "Default")
      (node (ref "U$2") (pin "36-PWM") (pinfunction "36-PWM_36-PWM") (pintype "bidirectional"))
    )
    (net (code "112") (name "unconnected-(U$2-Pad37-PWM)") (class "Default")
      (node (ref "U$2") (pin "37-PWM") (pinfunction "37-PWM_37-PWM") (pintype "bidirectional"))
    )
    (net (code "113") (name "unconnected-(U$2-PadDM)") (class "Default")
      (node (ref "U$2") (pin "DM") (pinfunction "DM_DM") (pintype "bidirectional"))
    )
    (net (code "114") (name "unconnected-(U$2-PadDP)") (class "Default")
      (node (ref "U$2") (pin "DP") (pinfunction "DP_DP") (pintype "bidirectional"))
    )
    (net (code "115") (name "unconnected-(U$2-PadGND1)") (class "Default")
      (node (ref "U$2") (pin "GND1") (pinfunction "GND1_GND1") (pintype "bidirectional"))
    )
    (net (code "116") (name "unconnected-(U$2-PadGND2)") (class "Default")
      (node (ref "U$2") (pin "GND2") (pinfunction "GND2_GND2") (pintype "bidirectional"))
    )
    (net (code "117") (name "unconnected-(U$2-PadGND3)") (class "Default")
      (node (ref "U$2") (pin "GND3") (pinfunction "GND3_GND3") (pintype "bidirectional"))
    )
    (net (code "118") (name "unconnected-(U$2-PadGND4)") (class "Default")
      (node (ref "U$2") (pin "GND4") (pinfunction "GND4_GND4") (pintype "bidirectional"))
    )
    (net (code "119") (name "unconnected-(U$2-PadGND5)") (class "Default")
      (node (ref "U$2") (pin "GND5") (pinfunction "GND5_GND5") (pintype "bidirectional"))
    )
    (net (code "120") (name "unconnected-(U$2-PadGND6)") (class "Default")
      (node (ref "U$2") (pin "GND6") (pinfunction "GND6_GND6") (pintype "bidirectional"))
    )
    (net (code "121") (name "unconnected-(U$2-PadON{slash}OFF)") (class "Default")
      (node (ref "U$2") (pin "ON/OFF") (pinfunction "ON/OFF_ON/OFF") (pintype "bidirectional"))
    )
    (net (code "122") (name "unconnected-(U$2-PadPROGRAM)") (class "Default")
      (node (ref "U$2") (pin "PROGRAM") (pinfunction "PROGRAM_PROGRAM") (pintype "bidirectional"))
    )
    (net (code "123") (name "unconnected-(U$2-PadVBAT)") (class "Default")
      (node (ref "U$2") (pin "VBAT") (pinfunction "VBAT_VBAT") (pintype "bidirectional"))
    )
    (net (code "124") (name "unconnected-(U$2-PadVUSB)") (class "Default")
      (node (ref "U$2") (pin "VUSB") (pinfunction "VUSB_VUSB") (pintype "bidirectional"))
    )
    (net (code "125") (name "unconnected-(U2-CPFILT-Pad18)") (class "Default")
      (node (ref "U2") (pin "18") (pinfunction "CPFILT_18") (pintype "bidirectional"))
    )
    (net (code "126") (name "unconnected-(U2-HP_L-Pad6)") (class "Default")
      (node (ref "U2") (pin "6") (pinfunction "HP_L_6") (pintype "output"))
    )
    (net (code "127") (name "unconnected-(U2-HP_R-Pad2)") (class "Default")
      (node (ref "U2") (pin "2") (pinfunction "HP_R_2") (pintype "output"))
    )
    (net (code "128") (name "unconnected-(U2-MIC-Pad15)") (class "Default")
      (node (ref "U2") (pin "15") (pinfunction "MIC_15") (pintype "input"))
    )
    (net (code "129") (name "unconnected-(U2-MIC_BIAS-Pad16)") (class "Default")
      (node (ref "U2") (pin "16") (pinfunction "MIC_BIAS_16") (pintype "bidirectional"))
    )
    (net (code "130") (name "unconnected-(U2-NC_8-Pad8)") (class "Default")
      (node (ref "U2") (pin "8") (pinfunction "NC_8_8") (pintype "passive"))
    )
    (net (code "131") (name "unconnected-(U2-NC_9-Pad9)") (class "Default")
      (node (ref "U2") (pin "9") (pinfunction "NC_9_9") (pintype "passive"))
    )
    (net (code "132") (name "unconnected-(U2-NC_17-Pad17)") (class "Default")
      (node (ref "U2") (pin "17") (pinfunction "NC_17_17") (pintype "passive"))
    )
    (net (code "133") (name "unconnected-(U2-NC_19-Pad19)") (class "Default")
      (node (ref "U2") (pin "19") (pinfunction "NC_19_19") (pintype "passive"))
    )
    (net (code "134") (name "unconnected-(U2-NC_22-Pad22)") (class "Default")
      (node (ref "U2") (pin "22") (pinfunction "NC_22_22") (pintype "passive"))
    )
    (net (code "135") (name "unconnected-(U2-NC_28-Pad28)") (class "Default")
      (node (ref "U2") (pin "28") (pinfunction "NC_28_28") (pintype "passive"))
    )
    (net (code "136") (name "unconnected-(X1-Pad3)") (class "Default")
      (node (ref "X1") (pin "3") (pinfunction "3_3") (pintype "passive"))
    )
    (net (code "137") (name "unconnected-(X1-Pad8)") (class "Default")
      (node (ref "X1") (pin "8") (pinfunction "8_8") (pintype "passive"))
    )
    (net (code "138") (name "unconnected-(X1-Pad9)") (class "Default")
      (node (ref "X1") (pin "9") (pinfunction "9_9") (pintype "passive"))
    )
    (net (code "139") (name "unconnected-(X1-Pad10)") (class "Default")
      (node (ref "X1") (pin "10") (pinfunction "10_10") (pintype "passive"))
    )
    (net (code "140") (name "unconnected-(X1-Pad11)") (class "Default")
      (node (ref "X1") (pin "11") (pinfunction "11_11") (pintype "passive"))
    )
    (net (code "141") (name "unconnected-(X1-Pad12)") (class "Default")
      (node (ref "X1") (pin "12") (pinfunction "12_12") (pintype "passive"))
    )
    (net (code "142") (name "unconnected-(X1-Pad16)") (class "Default")
      (node (ref "X1") (pin "16") (pinfunction "16_16") (pintype "passive"))
    )
    (net (code "143") (name "unconnected-(X1-Pad21)") (class "Default")
      (node (ref "X1") (pin "21") (pinfunction "21_21") (pintype "passive"))
    )
    (net (code "144") (name "unconnected-(X1-Pad22)") (class "Default")
      (node (ref "X1") (pin "22") (pinfunction "22_22") (pintype "passive"))
    )
    (net (code "145") (name "unconnected-(X1-Pad23)") (class "Default")
      (node (ref "X1") (pin "23") (pinfunction "23_23") (pintype "passive"))
    )
    (net (code "146") (name "unconnected-(X1-Pad24)") (class "Default")
      (node (ref "X1") (pin "24") (pinfunction "24_24") (pintype "passive"))
    )
    (net (code "147") (name "~{LDAC}") (class "Default")
      (node (ref "IC7") (pin "8") (pinfunction "~{LDAC}_8") (pintype "bidirectional"))
    )
  )
)
